# SolVoeding.net
KiCad netlist of a schematic drawn in Altium Designer
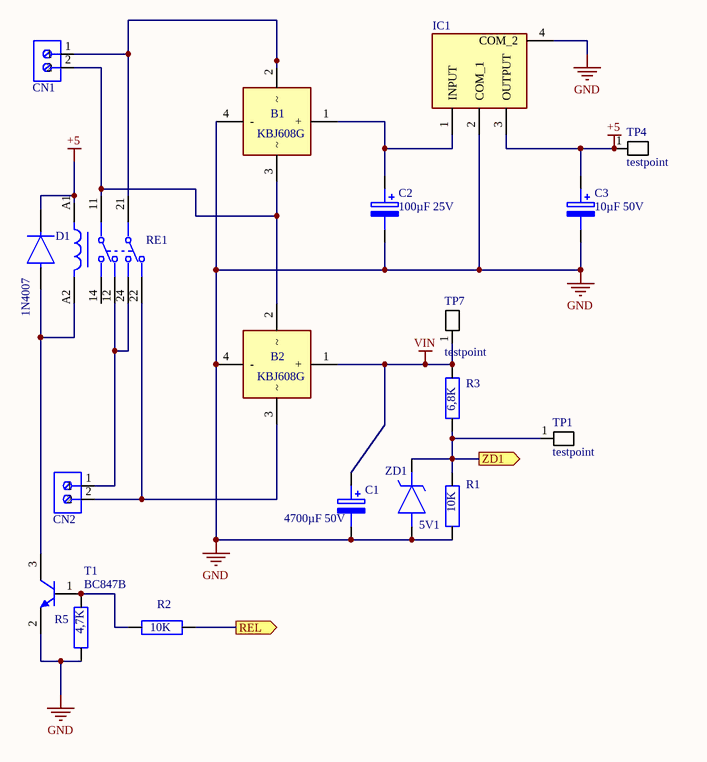
[diagram p0: SolVoeding.SchDoc]

(export (version "E")
  (design (tool "Eeschema 10.0.6"))
  (components
    (comp (ref "B1")
      (value "KBJ608G")
      (footprint "SamacSys:TO750P480X2500X1900-4P")
      (description "Bridge Rectifier")
      (fields (field (name "MOUSER2 PART NUMBER") "621-KBJ608G"))
      (libsource (lib "SamacSys") (part "KBJ608G"))
    )
    (comp (ref "B2")
      (value "KBJ608G")
      (footprint "SamacSys:TO750P480X2500X1900-4P")
      (description "Bridge Rectifier")
      (fields (field (name "MOUSER2 PART NUMBER") "621-KBJ608G"))
      (libsource (lib "SamacSys") (part "KBJ608G"))
    )
    (comp (ref "C1")
      (value "4700µF 50V")
      (footprint "Capacitor4700")
      (description "Capacitor Polarised")
      (fields
        (field (name "MANUFACTURER_PART_NUMBER") "T494D227K006AT")
        (field (name "MOUSER PART NUMBER") "80-T494D227K006")
      )
      (libsource (lib "soldeerstation") (part "ELCO4700uF"))
    )
    (comp (ref "C2")
      (value "100µF 25V")
      (footprint "caprad100mil")
      (description "Capacitor Polarised")
      (fields
        (field (name "MANUFACTURER_PART_NUMBER") "T494D227K006AT")
        (field (name "MOUSER PART NUMBER") "80-T494D227K006")
      )
      (libsource (lib "Schlib1") (part "ELCO220uF"))
    )
    (comp (ref "C3")
      (value "10µF 50V")
      (footprint "caprad100mil")
      (description "Capacitor Polarised")
      (fields
        (field (name "MANUFACTURER_PART_NUMBER") "T494D227K006AT")
        (field (name "MOUSER PART NUMBER") "80-T494D227K006")
      )
      (libsource (lib "Schlib1") (part "ELCO220uF"))
    )
    (comp (ref "CN1")
      (value "282836-2")
      (footprint "cnn2pin")
      (description "Female Header, Pitch 5 mm, 1 x 2 Position, Height 10 mm, Tail Length 3.5 mm, Rohs, Bulk")
      (fields (field (name "VOLTAGE") "300V") (field (name "MANUFACTURER") "TE Connectivity"))
      (libsource (lib "soldeerstation") (part "CNN2P"))
    )
    (comp (ref "CN2")
      (value "282836-2")
      (footprint "cnn2pin")
      (description "Female Header, Pitch 5 mm, 1 x 2 Position, Height 10 mm, Tail Length 3.5 mm, Rohs, Bulk")
      (fields (field (name "VOLTAGE") "300V") (field (name "MANUFACTURER") "TE Connectivity"))
      (libsource (lib "soldeerstation") (part "CNN2P"))
    )
    (comp (ref "D1")
      (value "1N4007")
      (footprint "FP-1N4007-MFG")
      (description "Rectifier diode 1000 V 1 A DO-41, ,")
      (fields
        (field (name "MANUFACTURER") "Diotec")
        (field (name "OCTOPART") "https://octopart.com/1n4007-diotec-4040411")
      )
      (libsource (lib "Altium Content Vault") (part "d7152d700b627762746794eb795d46e"))
    )
    (comp (ref "IC1")
      (value "TL780-05CKTTR")
      (footprint "SamacSys:TL78005CKTTR")
      (description "Integrated Circuit")
      (libsource (lib "soldeerstation") (part "TL780-05CKTTR"))
    )
    (comp (ref "R1")
      (value "10K")
      (footprint "res0805ph")
      (description "Resistor")
      (fields (field (name "MANUFACTURER_PART_NUMBER") "CPF0201D10K2C1"))
      (libsource (lib "") (part "Res_2"))
    )
    (comp (ref "R2")
      (value "10K")
      (footprint "res0805ph")
      (description "Resistor")
      (fields (field (name "MANUFACTURER_PART_NUMBER") "CPF0201D10K2C1"))
      (libsource (lib "") (part "Res_1"))
    )
    (comp (ref "R3")
      (value "6,8K")
      (footprint "res0805ph")
      (description "Resistor")
      (fields (field (name "MANUFACTURER_PART_NUMBER") "CPF0201D10K2C1"))
      (libsource (lib "soldeerstation") (part "Res"))
    )
    (comp (ref "R5")
      (value "4,7K")
      (footprint "res0805ph")
      (description "Resistor")
      (fields (field (name "MANUFACTURER_PART_NUMBER") "CPF0201D10K2C1"))
      (libsource (lib "soldeerstation") (part "Res"))
    )
    (comp (ref "RE1")
      (value "RT424615")
      (footprint "FP-RT424615-MFG")
      (description "RELAY GEN PURPOSE DPDT 8A 115V")
      (libsource (lib "Altium Content Vault") (part "41b11f646d56a8146f21bf1e8c88c79"))
    )
    (comp (ref "T1")
      (value "BC847B")
      (footprint "sot23")
      (description "NPN Silicon AF Transistor, 45 V VCEO, 100 mA IC, SOT23, Reel, Green")
      (fields (field (name "MANUFACTURER") "Infineon"))
      (libsource (lib "soldeerstation") (part "BC847"))
    )
    (comp (ref "TP1")
      (value "testpoint")
      (footprint "testpin")
      (libsource (lib "soldeerstation") (part "testpoint"))
    )
    (comp (ref "TP4")
      (value "testpoint")
      (footprint "testpin")
      (libsource (lib "soldeerstation") (part "testpoint"))
    )
    (comp (ref "TP7")
      (value "testpoint")
      (footprint "testpin")
      (libsource (lib "soldeerstation") (part "testpoint"))
    )
    (comp (ref "ZD1")
      (value "5V1")
      (footprint "SamacSys:DIOAD1068W53L380D172")
      (description "Zener Diode")
      (fields
        (field (name "MANUFACTURER_PART_NUMBER") "BZX79C6V8")
        (field (name "MOUSER PART NUMBER") "512-BZX79C6V8")
      )
      (libsource (lib "Schlib1") (part "BZX79C3V3"))
    )
  )
  (nets
    (net (code "1") (name "+5") (class "Default")
      (node (ref "C3") (pin "1") (pinfunction "+_1") (pintype "passive"))
      (node (ref "D1") (pin "1") (pinfunction "C_1") (pintype "passive"))
      (node (ref "IC1") (pin "3") (pinfunction "OUTPUT_3") (pintype "passive"))
      (node (ref "RE1") (pin "A1") (pinfunction "A1_A1") (pintype "passive"))
      (node (ref "TP4") (pin "1") (pinfunction "TP_1") (pintype "passive"))
    )
    (net (code "2") (name "/REL") (class "Default")
      (node (ref "R2") (pin "2") (pinfunction "2_2") (pintype "passive"))
    )
    (net (code "3") (name "/ZD1") (class "Default")
      (node (ref "R1") (pin "2") (pinfunction "2_2") (pintype "passive"))
      (node (ref "R3") (pin "2") (pinfunction "2_2") (pintype "passive"))
      (node (ref "TP1") (pin "1") (pinfunction "TP_1") (pintype "passive"))
      (node (ref "ZD1") (pin "1") (pinfunction "K_1") (pintype "passive"))
    )
    (net (code "4") (name "GND") (class "Default")
      (node (ref "B1") (pin "4") (pinfunction "-_4") (pintype "passive"))
      (node (ref "B2") (pin "4") (pinfunction "-_4") (pintype "passive"))
      (node (ref "C1") (pin "2") (pinfunction "-_2") (pintype "passive"))
      (node (ref "C2") (pin "2") (pinfunction "-_2") (pintype "passive"))
      (node (ref "C3") (pin "2") (pinfunction "-_2") (pintype "passive"))
      (node (ref "IC1") (pin "2") (pinfunction "COM_1_2") (pintype "passive"))
      (node (ref "IC1") (pin "4") (pinfunction "COM_2_4") (pintype "passive"))
      (node (ref "R1") (pin "1") (pinfunction "1_1") (pintype "passive"))
      (node (ref "R5") (pin "2") (pinfunction "2_2") (pintype "passive"))
      (node (ref "T1") (pin "2") (pinfunction "E_2") (pintype "passive"))
      (node (ref "ZD1") (pin "2") (pinfunction "A_2") (pintype "passive"))
    )
    (net (code "5") (name "Net-(B1-+)") (class "Default")
      (node (ref "B1") (pin "1") (pinfunction "+_1") (pintype "passive"))
      (node (ref "C2") (pin "1") (pinfunction "+_1") (pintype "passive"))
      (node (ref "IC1") (pin "1") (pinfunction "INPUT_1") (pintype "passive"))
    )
    (net (code "6") (name "Net-(B1-~-Pad2)") (class "Default")
      (node (ref "B1") (pin "2") (pinfunction "~_2") (pintype "passive"))
      (node (ref "CN1") (pin "1") (pinfunction "1_1") (pintype "passive"))
      (node (ref "RE1") (pin "21") (pinfunction "21_21") (pintype "passive"))
    )
    (net (code "7") (name "Net-(B1-~-Pad3)") (class "Default")
      (node (ref "B1") (pin "3") (pinfunction "~_3") (pintype "passive"))
      (node (ref "B2") (pin "2") (pinfunction "~_2") (pintype "passive"))
      (node (ref "CN1") (pin "2") (pinfunction "2_2") (pintype "passive"))
      (node (ref "RE1") (pin "11") (pinfunction "11_11") (pintype "passive"))
    )
    (net (code "8") (name "Net-(B2-~-Pad3)") (class "Default")
      (node (ref "B2") (pin "3") (pinfunction "~_3") (pintype "passive"))
      (node (ref "CN2") (pin "2") (pinfunction "2_2") (pintype "passive"))
      (node (ref "RE1") (pin "22") (pinfunction "22_22") (pintype "passive"))
    )
    (net (code "9") (name "Net-(CN2-Pad1)") (class "Default")
      (node (ref "CN2") (pin "1") (pinfunction "1_1") (pintype "passive"))
      (node (ref "RE1") (pin "12") (pinfunction "12_12") (pintype "passive"))
      (node (ref "RE1") (pin "24") (pinfunction "24_24") (pintype "passive"))
    )
    (net (code "10") (name "Net-(D1-A)") (class "Default")
      (node (ref "D1") (pin "2") (pinfunction "A_2") (pintype "passive"))
      (node (ref "RE1") (pin "A2") (pinfunction "A2_A2") (pintype "passive"))
      (node (ref "T1") (pin "3") (pinfunction "C_3") (pintype "passive"))
    )
    (net (code "11") (name "Net-(T1-B)") (class "Default")
      (node (ref "R2") (pin "1") (pinfunction "1_1") (pintype "passive"))
      (node (ref "R5") (pin "1") (pinfunction "1_1") (pintype "passive"))
      (node (ref "T1") (pin "1") (pinfunction "B_1") (pintype "passive"))
    )
    (net (code "12") (name "VIN") (class "Default")
      (node (ref "B2") (pin "1") (pinfunction "+_1") (pintype "passive"))
      (node (ref "C1") (pin "1") (pinfunction "+_1") (pintype "passive"))
      (node (ref "R3") (pin "1") (pinfunction "1_1") (pintype "passive"))
      (node (ref "TP7") (pin "1") (pinfunction "TP_1") (pintype "passive"))
    )
    (net (code "13") (name "unconnected-(RE1-Pad14)") (class "Default")
      (node (ref "RE1") (pin "14") (pinfunction "14_14") (pintype "passive"))
    )
  )
)
